# OpenBookReader_v57.net
KiCad netlist of a schematic drawn in EAGLE
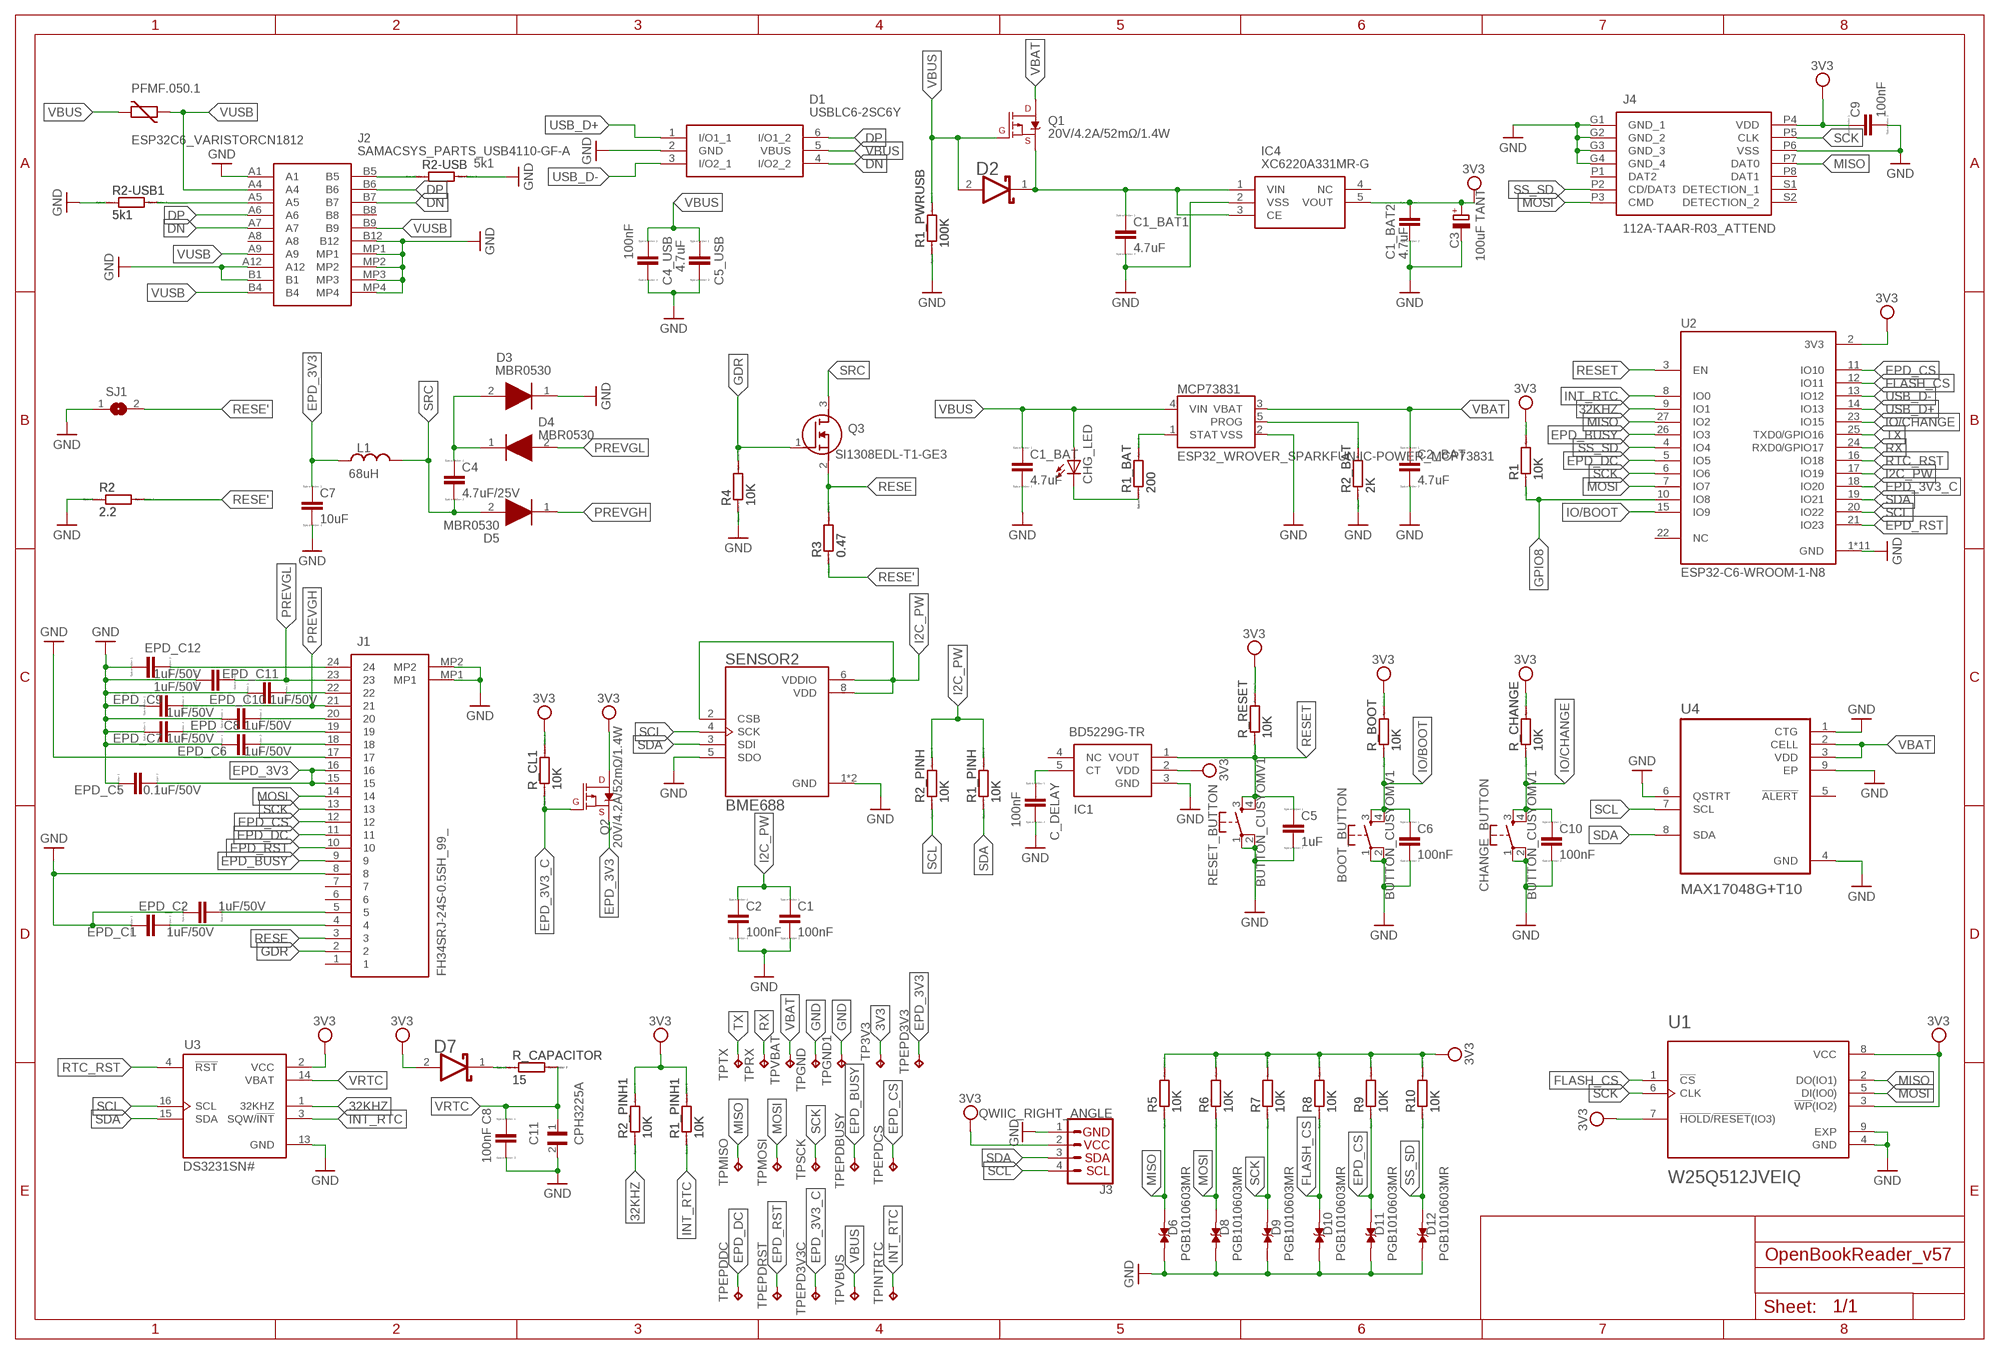
[diagram p0: schematic, sheet 1]

(export (version "E")
  (design (tool "Eeschema 10.0.6"))
  (components
    (comp (ref "BOOT_BUTTON")
      (value "BUTTON_CUSYOMV1")
      (footprint "eagle-import:MYBUTTON")
      (libsource (lib "eagle-import") (part "BUTTON_CUSYOMV1"))
    )
    (comp (ref "C1")
      (value "100nF")
      (footprint "eagle-import:EAGLE-LTSPICE_C0402")
      (libsource (lib "eagle-import") (part "EAGLE-LTSPICE_CC0402"))
    )
    (comp (ref "C1_BAT")
      (value "4.7uF")
      (footprint "eagle-import:EAGLE-LTSPICE_C0402")
      (libsource (lib "eagle-import") (part "EAGLE-LTSPICE_CC0402"))
    )
    (comp (ref "C1_BAT1")
      (value "4.7uF")
      (footprint "eagle-import:EAGLE-LTSPICE_C0402")
      (libsource (lib "eagle-import") (part "EAGLE-LTSPICE_CC0402"))
    )
    (comp (ref "C1_BAT2")
      (value "4.7uF")
      (footprint "eagle-import:EAGLE-LTSPICE_C0402")
      (libsource (lib "eagle-import") (part "EAGLE-LTSPICE_CC0402"))
    )
    (comp (ref "C2")
      (value "100nF")
      (footprint "eagle-import:EAGLE-LTSPICE_C0402")
      (libsource (lib "eagle-import") (part "EAGLE-LTSPICE_CC0402"))
    )
    (comp (ref "C2_BAT")
      (value "4.7uF")
      (footprint "eagle-import:EAGLE-LTSPICE_C0402")
      (libsource (lib "eagle-import") (part "EAGLE-LTSPICE_CC0402"))
    )
    (comp (ref "C3")
      (value "100uF TANT")
      (footprint "eagle-import:RCL_CT3528")
      (libsource (lib "eagle-import") (part "RCL_CPOL-EUCT3528"))
    )
    (comp (ref "C4")
      (value "4.7uF/25V")
      (footprint "eagle-import:EAGLE-LTSPICE_C0402")
      (libsource (lib "eagle-import") (part "EAGLE-LTSPICE_CC0402"))
    )
    (comp (ref "C4_USB")
      (value "100nF")
      (footprint "eagle-import:EAGLE-LTSPICE_C0402")
      (libsource (lib "eagle-import") (part "EAGLE-LTSPICE_CC0402"))
    )
    (comp (ref "C5")
      (value "1uF")
      (footprint "eagle-import:EAGLE-LTSPICE_C0402")
      (libsource (lib "eagle-import") (part "EAGLE-LTSPICE_CC0402"))
    )
    (comp (ref "C5_USB")
      (value "4.7uF")
      (footprint "eagle-import:EAGLE-LTSPICE_C0402")
      (libsource (lib "eagle-import") (part "EAGLE-LTSPICE_CC0402"))
    )
    (comp (ref "C6")
      (value "100nF")
      (footprint "eagle-import:EAGLE-LTSPICE_C0402")
      (libsource (lib "eagle-import") (part "EAGLE-LTSPICE_CC0402"))
    )
    (comp (ref "C7")
      (value "10uF")
      (footprint "eagle-import:EAGLE-LTSPICE_C0402")
      (libsource (lib "eagle-import") (part "EAGLE-LTSPICE_CC0402"))
    )
    (comp (ref "C8")
      (value "100nF")
      (footprint "eagle-import:EAGLE-LTSPICE_C0402")
      (libsource (lib "eagle-import") (part "EAGLE-LTSPICE_CC0402"))
    )
    (comp (ref "C9")
      (value "100nF")
      (footprint "eagle-import:EAGLE-LTSPICE_C0402")
      (libsource (lib "eagle-import") (part "EAGLE-LTSPICE_CC0402"))
    )
    (comp (ref "C10")
      (value "100nF")
      (footprint "eagle-import:EAGLE-LTSPICE_C0402")
      (libsource (lib "eagle-import") (part "EAGLE-LTSPICE_CC0402"))
    )
    (comp (ref "C11")
      (value "CPH3225A")
      (footprint "eagle-import:CAPCP3225X100N")
      (fields (field (name "MF") "Seiko Instruments"))
      (libsource (lib "eagle-import") (part "CPH3225A"))
    )
    (comp (ref "CHANGE_BUTTON")
      (value "BUTTON_CUSYOMV1")
      (footprint "eagle-import:MYBUTTON")
      (libsource (lib "eagle-import") (part "BUTTON_CUSYOMV1"))
    )
    (comp (ref "CHG_LED")
      (value "ADAFRUIT_LEDCHIP-LED0603")
      (footprint "eagle-import:ADAFRUIT_CHIP-LED0603")
      (libsource (lib "eagle-import") (part "ADAFRUIT_LEDCHIP-LED0603"))
    )
    (comp (ref "C_DELAY")
      (value "100nF")
      (footprint "eagle-import:EAGLE-LTSPICE_C0402")
      (libsource (lib "eagle-import") (part "EAGLE-LTSPICE_CC0402"))
    )
    (comp (ref "D1")
      (value "USBLC6-2SC6Y")
      (footprint "eagle-import:SOT95P280X145-6N")
      (fields (field (name "MF") "STMicroelectronics"))
      (libsource (lib "eagle-import") (part "USBLC6-2SC6Y"))
    )
    (comp (ref "D2")
      (value "ESP32_WROVER_AVX---SD0805S020S1R0_AVX_SD0805S020S1R0_0_0AVX_SD0805S020S1R0_0_0")
      (footprint "eagle-import:ESP32_WROVER_AVX---SD0805S020S1R0_AVX_SD0805S020S1R0_0")
      (fields
        (field (name "DIGIKEY_PART_NUMBER") "478-7800-1-ND")
        (field (name "MF") "AVX")
        (field (name "MOUSER_PART_NUMBER") "581-SD0805S020S1R0")
      )
      (libsource (lib "eagle-import") (part "ESP32_WROVER_AVX---SD0805S020S1R0_AVX_SD0805S020S1R0_0_0AVX_SD0805S020S1R0_0_0"))
    )
    (comp (ref "D3")
      (value "MBR0530")
      (footprint "eagle-import:SOD3716X135N")
      (fields (field (name "MF") "ON Semiconductor"))
      (libsource (lib "eagle-import") (part "MBR0530"))
    )
    (comp (ref "D4")
      (value "MBR0530")
      (footprint "eagle-import:SOD3716X135N")
      (fields (field (name "MF") "ON Semiconductor"))
      (libsource (lib "eagle-import") (part "MBR0530"))
    )
    (comp (ref "D5")
      (value "MBR0530")
      (footprint "eagle-import:SOD3716X135N")
      (fields (field (name "MF") "ON Semiconductor"))
      (libsource (lib "eagle-import") (part "MBR0530"))
    )
    (comp (ref "D6")
      (value "PGB1010603MR")
      (footprint "eagle-import:DIOC1608X36N")
      (fields (field (name "MF") "Littelfuse Inc."))
      (libsource (lib "eagle-import") (part "PGB1010603MR"))
    )
    (comp (ref "D7")
      (value "ESP32_WROVER_AVX---SD0805S020S1R0_AVX_SD0805S020S1R0_0_0AVX_SD0805S020S1R0_0_0")
      (footprint "eagle-import:ESP32_WROVER_AVX---SD0805S020S1R0_AVX_SD0805S020S1R0_0")
      (fields
        (field (name "DIGIKEY_PART_NUMBER") "478-7800-1-ND")
        (field (name "MF") "AVX")
        (field (name "MOUSER_PART_NUMBER") "581-SD0805S020S1R0")
      )
      (libsource (lib "eagle-import") (part "ESP32_WROVER_AVX---SD0805S020S1R0_AVX_SD0805S020S1R0_0_0AVX_SD0805S020S1R0_0_0"))
    )
    (comp (ref "D8")
      (value "PGB1010603MR")
      (footprint "eagle-import:DIOC1608X36N")
      (fields (field (name "MF") "Littelfuse Inc."))
      (libsource (lib "eagle-import") (part "PGB1010603MR"))
    )
    (comp (ref "D9")
      (value "PGB1010603MR")
      (footprint "eagle-import:DIOC1608X36N")
      (fields (field (name "MF") "Littelfuse Inc."))
      (libsource (lib "eagle-import") (part "PGB1010603MR"))
    )
    (comp (ref "D10")
      (value "PGB1010603MR")
      (footprint "eagle-import:DIOC1608X36N")
      (fields (field (name "MF") "Littelfuse Inc."))
      (libsource (lib "eagle-import") (part "PGB1010603MR"))
    )
    (comp (ref "D11")
      (value "PGB1010603MR")
      (footprint "eagle-import:DIOC1608X36N")
      (fields (field (name "MF") "Littelfuse Inc."))
      (libsource (lib "eagle-import") (part "PGB1010603MR"))
    )
    (comp (ref "D12")
      (value "PGB1010603MR")
      (footprint "eagle-import:DIOC1608X36N")
      (fields (field (name "MF") "Littelfuse Inc."))
      (libsource (lib "eagle-import") (part "PGB1010603MR"))
    )
    (comp (ref "EPD_C1")
      (value "1uF/50V")
      (footprint "eagle-import:EAGLE-LTSPICE_C0402")
      (libsource (lib "eagle-import") (part "EAGLE-LTSPICE_CC0402"))
    )
    (comp (ref "EPD_C2")
      (value "1uF/50V")
      (footprint "eagle-import:EAGLE-LTSPICE_C0402")
      (libsource (lib "eagle-import") (part "EAGLE-LTSPICE_CC0402"))
    )
    (comp (ref "EPD_C5")
      (value "0.1uF/50V")
      (footprint "eagle-import:EAGLE-LTSPICE_C0402")
      (libsource (lib "eagle-import") (part "EAGLE-LTSPICE_CC0402"))
    )
    (comp (ref "EPD_C6")
      (value "1uF/50V")
      (footprint "eagle-import:EAGLE-LTSPICE_C0402")
      (libsource (lib "eagle-import") (part "EAGLE-LTSPICE_CC0402"))
    )
    (comp (ref "EPD_C7")
      (value "1uF/50V")
      (footprint "eagle-import:EAGLE-LTSPICE_C0402")
      (libsource (lib "eagle-import") (part "EAGLE-LTSPICE_CC0402"))
    )
    (comp (ref "EPD_C8")
      (value "1uF/50V")
      (footprint "eagle-import:EAGLE-LTSPICE_C0402")
      (libsource (lib "eagle-import") (part "EAGLE-LTSPICE_CC0402"))
    )
    (comp (ref "EPD_C9")
      (value "1uF/50V")
      (footprint "eagle-import:EAGLE-LTSPICE_C0402")
      (libsource (lib "eagle-import") (part "EAGLE-LTSPICE_CC0402"))
    )
    (comp (ref "EPD_C10")
      (value "1uF/50V")
      (footprint "eagle-import:EAGLE-LTSPICE_C0402")
      (libsource (lib "eagle-import") (part "EAGLE-LTSPICE_CC0402"))
    )
    (comp (ref "EPD_C11")
      (value "1uF/50V")
      (footprint "eagle-import:EAGLE-LTSPICE_C0402")
      (libsource (lib "eagle-import") (part "EAGLE-LTSPICE_CC0402"))
    )
    (comp (ref "EPD_C12")
      (value "1uF/50V")
      (footprint "eagle-import:EAGLE-LTSPICE_C0402")
      (libsource (lib "eagle-import") (part "EAGLE-LTSPICE_CC0402"))
    )
    (comp (ref "IC1")
      (value "BD5229G-TR")
      (footprint "eagle-import:SOT95P280X125-5N")
      (fields (field (name "MOUSER_PART_NUMBER") "755-BD5229G-TR"))
      (libsource (lib "eagle-import") (part "BD5229G-TR"))
    )
    (comp (ref "IC4")
      (value "XC6220A331MR-G")
      (footprint "eagle-import:SOT95P280X120-5N")
      (fields (field (name "MOUSER_PART_NUMBER") "865-XC6220A331MR-G"))
      (libsource (lib "eagle-import") (part "XC6220A331MR-G"))
    )
    (comp (ref "J1")
      (value "FH34SRJ-24S-0.5SH_99_")
      (footprint "eagle-import:FH34SRJ24S05SH99")
      (fields
        (field (name "MANUFACTURER_PART_NUMBER") "FH34SRJ-24S-0.5SH(99)")
        (field (name "MOUSER_PART_NUMBER") "798-FH34SRJ24S05SH99")
      )
      (libsource (lib "eagle-import") (part "FH34SRJ-24S-0.5SH_99_"))
    )
    (comp (ref "J2")
      (value "SAMACSYS_PARTS_USB4110-GF-A")
      (footprint "eagle-import:SAMACSYS_PARTS_USB4110GFA")
      (fields
        (field (name "MANUFACTURER_PART_NUMBER") "USB4110-GF-A")
        (field (name "MOUSER_PART_NUMBER") "640-USB4110-GF-A")
      )
      (libsource (lib "eagle-import") (part "SAMACSYS_PARTS_USB4110-GF-A"))
    )
    (comp (ref "J3")
      (value "QWIIC_RIGHT_ANGLE")
      (footprint "eagle-import:JST04_1MM_RA")
      (libsource (lib "eagle-import") (part "QWIIC_CONNECTORJS-1MM"))
    )
    (comp (ref "J4")
      (value "112A-TAAR-R03_ATTEND")
      (footprint "eagle-import:112ATAARR03ATTEND")
      (fields (field (name "MANUFACTURER_PART_NUMBER") "112A-TAAR-R03 ATTEND"))
      (libsource (lib "eagle-import") (part "112A-TAAR-R03_ATTEND"))
    )
    (comp (ref "L1")
      (value "68uH")
      (footprint "eagle-import:INDC1006X60N")
      (libsource (lib "eagle-import") (part "INDUCTORCHIP-0402(1006-METRIC)_"))
    )
    (comp (ref "MCP73831")
      (value "ESP32_WROVER_SPARKFUN-IC-POWER_MCP73831")
      (footprint "eagle-import:ESP32_WROVER_SPARKFUN-IC-POWER_SOT23-5")
      (libsource (lib "eagle-import") (part "ESP32_WROVER_SPARKFUN-IC-POWER_MCP73831"))
    )
    (comp (ref "PFMF.050.1")
      (value "ESP32C6_VARISTORCN1812")
      (footprint "eagle-import:ESP32C6_VARISTOR_CT_CN1812")
      (libsource (lib "eagle-import") (part "ESP32C6_VARISTORCN1812"))
    )
    (comp (ref "Q1")
      (value "20V/4.2A/52mΩ/1.4W")
      (footprint "eagle-import:ESP32_WROVER_SPARKFUN-DISCRETESEMI_SOT23-3")
      (libsource (lib "eagle-import") (part "ESP32_WROVER_SPARKFUN-DISCRETESEMI_MOSFET_PCH-DMG2305UX-7"))
    )
    (comp (ref "Q2")
      (value "20V/4.2A/52mΩ/1.4W")
      (footprint "eagle-import:ESP32_WROVER_SPARKFUN-DISCRETESEMI_SOT23-3")
      (libsource (lib "eagle-import") (part "ESP32_WROVER_SPARKFUN-DISCRETESEMI_MOSFET_PCH-DMG2305UX-7"))
    )
    (comp (ref "Q3")
      (value "SI1308EDL-T1-GE3")
      (footprint "eagle-import:SOT65P210X110-3N")
      (fields (field (name "MF") "Vishay Siliconix"))
      (libsource (lib "eagle-import") (part "SI1308EDL-T1-GE3"))
    )
    (comp (ref "R1")
      (value "10K")
      (footprint "eagle-import:ESP32_WROVER_EAGLE-LTSPICE_R0402")
      (libsource (lib "eagle-import") (part "ESP32_WROVER_EAGLE-LTSPICE_RR0402"))
    )
    (comp (ref "R1_BAT")
      (value "200")
      (footprint "eagle-import:ESP32_WROVER_EAGLE-LTSPICE_R0402")
      (libsource (lib "eagle-import") (part "ESP32_WROVER_EAGLE-LTSPICE_RR0402"))
    )
    (comp (ref "R1_PINH")
      (value "10K")
      (footprint "eagle-import:ESP32_WROVER_EAGLE-LTSPICE_R0402")
      (libsource (lib "eagle-import") (part "ESP32_WROVER_EAGLE-LTSPICE_RR0402"))
    )
    (comp (ref "R1_PINH1")
      (value "10K")
      (footprint "eagle-import:ESP32_WROVER_EAGLE-LTSPICE_R0402")
      (libsource (lib "eagle-import") (part "ESP32_WROVER_EAGLE-LTSPICE_RR0402"))
    )
    (comp (ref "R1_PWRUSB")
      (value "100K")
      (footprint "eagle-import:ESP32_WROVER_EAGLE-LTSPICE_R0402")
      (libsource (lib "eagle-import") (part "ESP32_WROVER_EAGLE-LTSPICE_RR0402"))
    )
    (comp (ref "R2")
      (value "2.2")
      (footprint "eagle-import:ESP32_WROVER_EAGLE-LTSPICE_R0402")
      (libsource (lib "eagle-import") (part "ESP32_WROVER_EAGLE-LTSPICE_RR0402"))
    )
    (comp (ref "R2-USB")
      (value "5k1")
      (footprint "eagle-import:ESP32_WROVER_EAGLE-LTSPICE_R0402")
      (libsource (lib "eagle-import") (part "ESP32_WROVER_EAGLE-LTSPICE_RR0402"))
    )
    (comp (ref "R2-USB1")
      (value "5k1")
      (footprint "eagle-import:ESP32_WROVER_EAGLE-LTSPICE_R0402")
      (libsource (lib "eagle-import") (part "ESP32_WROVER_EAGLE-LTSPICE_RR0402"))
    )
    (comp (ref "R2_BAT")
      (value "2K")
      (footprint "eagle-import:ESP32_WROVER_EAGLE-LTSPICE_R0402")
      (libsource (lib "eagle-import") (part "ESP32_WROVER_EAGLE-LTSPICE_RR0402"))
    )
    (comp (ref "R2_PINH")
      (value "10K")
      (footprint "eagle-import:ESP32_WROVER_EAGLE-LTSPICE_R0402")
      (libsource (lib "eagle-import") (part "ESP32_WROVER_EAGLE-LTSPICE_RR0402"))
    )
    (comp (ref "R2_PINH1")
      (value "10K")
      (footprint "eagle-import:ESP32_WROVER_EAGLE-LTSPICE_R0402")
      (libsource (lib "eagle-import") (part "ESP32_WROVER_EAGLE-LTSPICE_RR0402"))
    )
    (comp (ref "R3")
      (value "0.47")
      (footprint "eagle-import:ESP32_WROVER_EAGLE-LTSPICE_R0402")
      (libsource (lib "eagle-import") (part "ESP32_WROVER_EAGLE-LTSPICE_RR0402"))
    )
    (comp (ref "R4")
      (value "10K")
      (footprint "eagle-import:ESP32_WROVER_EAGLE-LTSPICE_R0402")
      (libsource (lib "eagle-import") (part "ESP32_WROVER_EAGLE-LTSPICE_RR0402"))
    )
    (comp (ref "R5")
      (value "10K")
      (footprint "eagle-import:ESP32_WROVER_EAGLE-LTSPICE_R0402")
      (libsource (lib "eagle-import") (part "ESP32_WROVER_EAGLE-LTSPICE_RR0402"))
    )
    (comp (ref "R6")
      (value "10K")
      (footprint "eagle-import:ESP32_WROVER_EAGLE-LTSPICE_R0402")
      (libsource (lib "eagle-import") (part "ESP32_WROVER_EAGLE-LTSPICE_RR0402"))
    )
    (comp (ref "R7")
      (value "10K")
      (footprint "eagle-import:ESP32_WROVER_EAGLE-LTSPICE_R0402")
      (libsource (lib "eagle-import") (part "ESP32_WROVER_EAGLE-LTSPICE_RR0402"))
    )
    (comp (ref "R8")
      (value "10K")
      (footprint "eagle-import:ESP32_WROVER_EAGLE-LTSPICE_R0402")
      (libsource (lib "eagle-import") (part "ESP32_WROVER_EAGLE-LTSPICE_RR0402"))
    )
    (comp (ref "R9")
      (value "10K")
      (footprint "eagle-import:ESP32_WROVER_EAGLE-LTSPICE_R0402")
      (libsource (lib "eagle-import") (part "ESP32_WROVER_EAGLE-LTSPICE_RR0402"))
    )
    (comp (ref "R10")
      (value "10K")
      (footprint "eagle-import:ESP32_WROVER_EAGLE-LTSPICE_R0402")
      (libsource (lib "eagle-import") (part "ESP32_WROVER_EAGLE-LTSPICE_RR0402"))
    )
    (comp (ref "RESET_BUTTON")
      (value "BUTTON_CUSYOMV1")
      (footprint "eagle-import:MYBUTTON")
      (libsource (lib "eagle-import") (part "BUTTON_CUSYOMV1"))
    )
    (comp (ref "R_BOOT")
      (value "10K")
      (footprint "eagle-import:ESP32_WROVER_EAGLE-LTSPICE_R0402")
      (libsource (lib "eagle-import") (part "ESP32_WROVER_EAGLE-LTSPICE_RR0402"))
    )
    (comp (ref "R_CAPACITOR")
      (value "15")
      (footprint "eagle-import:ESP32_WROVER_EAGLE-LTSPICE_R0402")
      (libsource (lib "eagle-import") (part "ESP32_WROVER_EAGLE-LTSPICE_RR0402"))
    )
    (comp (ref "R_CHANGE")
      (value "10K")
      (footprint "eagle-import:ESP32_WROVER_EAGLE-LTSPICE_R0402")
      (libsource (lib "eagle-import") (part "ESP32_WROVER_EAGLE-LTSPICE_RR0402"))
    )
    (comp (ref "R_CL1")
      (value "10K")
      (footprint "eagle-import:ESP32_WROVER_EAGLE-LTSPICE_R0402")
      (libsource (lib "eagle-import") (part "ESP32_WROVER_EAGLE-LTSPICE_RR0402"))
    )
    (comp (ref "R_RESET")
      (value "10K")
      (footprint "eagle-import:ESP32_WROVER_EAGLE-LTSPICE_R0402")
      (libsource (lib "eagle-import") (part "ESP32_WROVER_EAGLE-LTSPICE_RR0402"))
    )
    (comp (ref "SENSOR2")
      (value "BME688")
      (footprint "eagle-import:ESP32_WROVER_BME680_PSON80P300X300X100-8N")
      (fields (field (name "MF") "Bosch Sensortec") (field (name "MP") "BME680"))
      (libsource (lib "eagle-import") (part "ESP32_WROVER_BME680_BME680"))
    )
    (comp (ref "SJ1") (value "SJ") (footprint "eagle-import:SJ") (libsource (lib "eagle-import") (part "SJ")))
    (comp (ref "TP3V3")
      (value "TPTP20R")
      (footprint "eagle-import:TP20R")
      (libsource (lib "eagle-import") (part "TPTP20R"))
    )
    (comp (ref "TPEPD3V3")
      (value "TPTP20R")
      (footprint "eagle-import:TP20R")
      (libsource (lib "eagle-import") (part "TPTP20R"))
    )
    (comp (ref "TPEPD3V3C")
      (value "TPTP20R")
      (footprint "eagle-import:TP20R")
      (libsource (lib "eagle-import") (part "TPTP20R"))
    )
    (comp (ref "TPEPDBUSY")
      (value "TPTP20R")
      (footprint "eagle-import:TP20R")
      (libsource (lib "eagle-import") (part "TPTP20R"))
    )
    (comp (ref "TPEPDCS")
      (value "TPTP20R")
      (footprint "eagle-import:TP20R")
      (libsource (lib "eagle-import") (part "TPTP20R"))
    )
    (comp (ref "TPEPDDC")
      (value "TPTP20R")
      (footprint "eagle-import:TP20R")
      (libsource (lib "eagle-import") (part "TPTP20R"))
    )
    (comp (ref "TPEPDRST")
      (value "TPTP20R")
      (footprint "eagle-import:TP20R")
      (libsource (lib "eagle-import") (part "TPTP20R"))
    )
    (comp (ref "TPGND")
      (value "TPTP20R")
      (footprint "eagle-import:TP20R")
      (libsource (lib "eagle-import") (part "TPTP20R"))
    )
    (comp (ref "TPGND1")
      (value "TPTP20R")
      (footprint "eagle-import:TP20R")
      (libsource (lib "eagle-import") (part "TPTP20R"))
    )
    (comp (ref "TPINTRTC")
      (value "TPTP20R")
      (footprint "eagle-import:TP20R")
      (libsource (lib "eagle-import") (part "TPTP20R"))
    )
    (comp (ref "TPMISO")
      (value "TPTP20R")
      (footprint "eagle-import:TP20R")
      (libsource (lib "eagle-import") (part "TPTP20R"))
    )
    (comp (ref "TPMOSI")
      (value "TPTP20R")
      (footprint "eagle-import:TP20R")
      (libsource (lib "eagle-import") (part "TPTP20R"))
    )
    (comp (ref "TPRX")
      (value "TPTP20R")
      (footprint "eagle-import:TP20R")
      (libsource (lib "eagle-import") (part "TPTP20R"))
    )
    (comp (ref "TPSCK")
      (value "TPTP20R")
      (footprint "eagle-import:TP20R")
      (libsource (lib "eagle-import") (part "TPTP20R"))
    )
    (comp (ref "TPTX")
      (value "TPTP20R")
      (footprint "eagle-import:TP20R")
      (libsource (lib "eagle-import") (part "TPTP20R"))
    )
    (comp (ref "TPVBAT")
      (value "TPTP20R")
      (footprint "eagle-import:TP20R")
      (libsource (lib "eagle-import") (part "TPTP20R"))
    )
    (comp (ref "TPVBUS")
      (value "TPTP20R")
      (footprint "eagle-import:TP20R")
      (libsource (lib "eagle-import") (part "TPTP20R"))
    )
    (comp (ref "U1")
      (value "W25Q512JVEIQ")
      (footprint "eagle-import:SON127P600X800X80-9N")
      (fields (field (name "MF") "Winbond Electronics"))
      (libsource (lib "eagle-import") (part "W25Q512JVEIQ"))
    )
    (comp (ref "U2")
      (value "ESP32-C6-WROOM-1-N8")
      (footprint "eagle-import:XCVR_ESP32-C6-WROOM-1-N8")
      (fields (field (name "MF") "Espressif Systems"))
      (libsource (lib "eagle-import") (part "ESP32-C6-WROOM-1-N8"))
    )
    (comp (ref "U3")
      (value "DS3231SN#")
      (footprint "eagle-import:SOIC127P1032X265-16N")
      (fields (field (name "MF") "Analog Devices"))
      (libsource (lib "eagle-import") (part "DS3231SN#"))
    )
    (comp (ref "U4")
      (value "MAX17048G+T10")
      (footprint "eagle-import:SON50P200X200X80-9N")
      (fields (field (name "MF") "Analog Devices"))
      (libsource (lib "eagle-import") (part "MAX17048G+T10"))
    )
  )
  (nets
    (net (code "1") (name "3V3") (class "Default")
      (node (ref "C1_BAT2") (pin "1") (pinfunction "1_1") (pintype "passive"))
      (node (ref "C3") (pin "+") (pinfunction "+_+") (pintype "passive"))
      (node (ref "C9") (pin "1") (pinfunction "1_1") (pintype "passive"))
      (node (ref "D7") (pin "2") (pinfunction "ANODE_2") (pintype "bidirectional"))
      (node (ref "IC1") (pin "2") (pinfunction "VDD_2") (pintype "bidirectional"))
      (node (ref "IC4") (pin "5") (pinfunction "VOUT_5") (pintype "bidirectional"))
      (node (ref "J3") (pin "2") (pinfunction "2_2") (pintype "power_in"))
      (node (ref "J4") (pin "P4") (pinfunction "VDD_P4") (pintype "bidirectional"))
      (node (ref "Q2") (pin "3") (pinfunction "D_3") (pintype "bidirectional"))
      (node (ref "R1") (pin "2") (pinfunction "2_2") (pintype "passive"))
      (node (ref "R10") (pin "2") (pinfunction "2_2") (pintype "passive"))
      (node (ref "R1_PINH1") (pin "2") (pinfunction "2_2") (pintype "passive"))
      (node (ref "R2_PINH1") (pin "2") (pinfunction "2_2") (pintype "passive"))
      (node (ref "R5") (pin "2") (pinfunction "2_2") (pintype "passive"))
      (node (ref "R6") (pin "2") (pinfunction "2_2") (pintype "passive"))
      (node (ref "R7") (pin "2") (pinfunction "2_2") (pintype "passive"))
      (node (ref "R8") (pin "2") (pinfunction "2_2") (pintype "passive"))
      (node (ref "R9") (pin "2") (pinfunction "2_2") (pintype "passive"))
      (node (ref "R_BOOT") (pin "2") (pinfunction "2_2") (pintype "passive"))
      (node (ref "R_CHANGE") (pin "2") (pinfunction "2_2") (pintype "passive"))
      (node (ref "R_CL1") (pin "2") (pinfunction "2_2") (pintype "passive"))
      (node (ref "R_RESET") (pin "2") (pinfunction "2_2") (pintype "passive"))
      (node (ref "TP3V3") (pin "TP") (pinfunction "TP_TP") (pintype "input"))
      (node (ref "U1") (pin "3") (pinfunction "~{WP}(IO2)_3") (pintype "bidirectional"))
      (node (ref "U1") (pin "7") (pinfunction "~{HOLD}/~{RESET}(IO3)_7") (pintype "bidirectional"))
      (node (ref "U1") (pin "8") (pinfunction "VCC_8") (pintype "power_in"))
      (node (ref "U2") (pin "2") (pinfunction "3V3_2") (pintype "power_in"))
      (node (ref "U3") (pin "2") (pinfunction "VCC_2") (pintype "power_in"))
    )
    (net (code "2") (name "32KHZ") (class "Default")
      (node (ref "R2_PINH1") (pin "1") (pinfunction "1_1") (pintype "passive"))
      (node (ref "U2") (pin "9") (pinfunction "IO1_9") (pintype "bidirectional"))
      (node (ref "U3") (pin "1") (pinfunction "32KHZ_1") (pintype "output"))
    )
    (net (code "3") (name "DN") (class "Default")
      (node (ref "D1") (pin "4") (pinfunction "I/O2_2_4") (pintype "bidirectional"))
      (node (ref "J2") (pin "A7") (pinfunction "A7_A7") (pintype "bidirectional"))
      (node (ref "J2") (pin "B7") (pinfunction "B7_B7") (pintype "bidirectional"))
    )
    (net (code "4") (name "DP") (class "Default")
      (node (ref "D1") (pin "6") (pinfunction "I/O1_2_6") (pintype "bidirectional"))
      (node (ref "J2") (pin "A6") (pinfunction "A6_A6") (pintype "bidirectional"))
      (node (ref "J2") (pin "B6") (pinfunction "B6_B6") (pintype "bidirectional"))
    )
    (net (code "5") (name "EPD_3V3") (class "Default")
      (node (ref "C7") (pin "1") (pinfunction "1_1") (pintype "passive"))
      (node (ref "EPD_C5") (pin "2") (pinfunction "2_2") (pintype "passive"))
      (node (ref "J1") (pin "15") (pinfunction "15_15") (pintype "bidirectional"))
      (node (ref "J1") (pin "16") (pinfunction "16_16") (pintype "bidirectional"))
      (node (ref "L1") (pin "1") (pinfunction "1_1") (pintype "passive"))
      (node (ref "Q2") (pin "2") (pinfunction "S_2") (pintype "bidirectional"))
      (node (ref "TPEPD3V3") (pin "TP") (pinfunction "TP_TP") (pintype "input"))
    )
    (net (code "6") (name "EPD_3V3_C") (class "Default")
      (node (ref "Q2") (pin "1") (pinfunction "G_1") (pintype "bidirectional"))
      (node (ref "R_CL1") (pin "1") (pinfunction "1_1") (pintype "passive"))
      (node (ref "TPEPD3V3C") (pin "TP") (pinfunction "TP_TP") (pintype "input"))
      (node (ref "U2") (pin "18") (pinfunction "IO20_18") (pintype "bidirectional"))
    )
    (net (code "7") (name "EPD_BUSY") (class "Default")
      (node (ref "J1") (pin "9") (pinfunction "9_9") (pintype "bidirectional"))
      (node (ref "TPEPDBUSY") (pin "TP") (pinfunction "TP_TP") (pintype "input"))
      (node (ref "U2") (pin "26") (pinfunction "IO3_26") (pintype "bidirectional"))
    )
    (net (code "8") (name "EPD_CS") (class "Default")
      (node (ref "D11") (pin "2") (pinfunction "2_2") (pintype "passive"))
      (node (ref "J1") (pin "12") (pinfunction "12_12") (pintype "bidirectional"))
      (node (ref "R9") (pin "1") (pinfunction "1_1") (pintype "passive"))
      (node (ref "TPEPDCS") (pin "TP") (pinfunction "TP_TP") (pintype "input"))
      (node (ref "U2") (pin "11") (pinfunction "IO10_11") (pintype "bidirectional"))
    )
    (net (code "9") (name "EPD_DC") (class "Default")
      (node (ref "J1") (pin "11") (pinfunction "11_11") (pintype "bidirectional"))
      (node (ref "TPEPDDC") (pin "TP") (pinfunction "TP_TP") (pintype "input"))
      (node (ref "U2") (pin "5") (pinfunction "IO5_5") (pintype "bidirectional"))
    )
    (net (code "10") (name "EPD_RST") (class "Default")
      (node (ref "J1") (pin "10") (pinfunction "10_10") (pintype "bidirectional"))
      (node (ref "TPEPDRST") (pin "TP") (pinfunction "TP_TP") (pintype "input"))
      (node (ref "U2") (pin "21") (pinfunction "IO23_21") (pintype "bidirectional"))
    )
    (net (code "11") (name "FLASH_CS") (class "Default")
      (node (ref "D10") (pin "2") (pinfunction "2_2") (pintype "passive"))
      (node (ref "R8") (pin "1") (pinfunction "1_1") (pintype "passive"))
      (node (ref "U1") (pin "1") (pinfunction "~{CS}_1") (pintype "input"))
      (node (ref "U2") (pin "12") (pinfunction "IO11_12") (pintype "bidirectional"))
    )
    (net (code "12") (name "GDR") (class "Default")
      (node (ref "J1") (pin "2") (pinfunction "2_2") (pintype "bidirectional"))
      (node (ref "Q3") (pin "1") (pinfunction "G_1") (pintype "bidirectional"))
      (node (ref "R4") (pin "2") (pinfunction "2_2") (pintype "passive"))
    )
    (net (code "13") (name "GND") (class "Default")
      (node (ref "BOOT_BUTTON") (pin "1") (pinfunction "1_1") (pintype "passive"))
      (node (ref "BOOT_BUTTON") (pin "2") (pinfunction "2_2") (pintype "passive"))
      (node (ref "C1") (pin "2") (pinfunction "2_2") (pintype "passive"))
      (node (ref "C10") (pin "2") (pinfunction "2_2") (pintype "passive"))
      (node (ref "C11") (pin "2") (pinfunction "2_2") (pintype "passive"))
      (node (ref "C1_BAT") (pin "2") (pinfunction "2_2") (pintype "passive"))
      (node (ref "C1_BAT1") (pin "2") (pinfunction "2_2") (pintype "passive"))
      (node (ref "C1_BAT2") (pin "2") (pinfunction "2_2") (pintype "passive"))
      (node (ref "C2") (pin "2") (pinfunction "2_2") (pintype "passive"))
      (node (ref "C2_BAT") (pin "2") (pinfunction "2_2") (pintype "passive"))
      (node (ref "C3") (pin "-") (pinfunction "-_-") (pintype "passive"))
      (node (ref "C4_USB") (pin "2") (pinfunction "2_2") (pintype "passive"))
      (node (ref "C5") (pin "2") (pinfunction "2_2") (pintype "passive"))
      (node (ref "C5_USB") (pin "2") (pinfunction "2_2") (pintype "passive"))
      (node (ref "C6") (pin "2") (pinfunction "2_2") (pintype "passive"))
      (node (ref "C7") (pin "2") (pinfunction "2_2") (pintype "passive"))
      (node (ref "C8") (pin "2") (pinfunction "2_2") (pintype "passive"))
      (node (ref "C9") (pin "2") (pinfunction "2_2") (pintype "passive"))
      (node (ref "CHANGE_BUTTON") (pin "1") (pinfunction "1_1") (pintype "passive"))
      (node (ref "CHANGE_BUTTON") (pin "2") (pinfunction "2_2") (pintype "passive"))
      (node (ref "C_DELAY") (pin "2") (pinfunction "2_2") (pintype "passive"))
      (node (ref "D1") (pin "2") (pinfunction "GND_2") (pintype "bidirectional"))
      (node (ref "D10") (pin "1") (pinfunction "1_1") (pintype "passive"))
      (node (ref "D11") (pin "1") (pinfunction "1_1") (pintype "passive"))
      (node (ref "D12") (pin "1") (pinfunction "1_1") (pintype "passive"))
      (node (ref "D3") (pin "1") (pinfunction "K_1") (pintype "bidirectional"))
      (node (ref "D6") (pin "1") (pinfunction "1_1") (pintype "passive"))
      (node (ref "D8") (pin "1") (pinfunction "1_1") (pintype "passive"))
      (node (ref "D9") (pin "1") (pinfunction "1_1") (pintype "passive"))
      (node (ref "EPD_C1") (pin "1") (pinfunction "1_1") (pintype "passive"))
      (node (ref "EPD_C10") (pin "1") (pinfunction "1_1") (pintype "passive"))
      (node (ref "EPD_C11") (pin "1") (pinfunction "1_1") (pintype "passive"))
      (node (ref "EPD_C12") (pin "1") (pinfunction "1_1") (pintype "passive"))
      (node (ref "EPD_C2") (pin "1") (pinfunction "1_1") (pintype "passive"))
      (node (ref "EPD_C5") (pin "1") (pinfunction "1_1") (pintype "passive"))
      (node (ref "EPD_C6") (pin "1") (pinfunction "1_1") (pintype "passive"))
      (node (ref "EPD_C7") (pin "1") (pinfunction "1_1") (pintype "passive"))
      (node (ref "EPD_C8") (pin "1") (pinfunction "1_1") (pintype "passive"))
      (node (ref "EPD_C9") (pin "1") (pinfunction "1_1") (pintype "passive"))
      (node (ref "IC1") (pin "3") (pinfunction "GND_3") (pintype "bidirectional"))
      (node (ref "IC4") (pin "2") (pinfunction "VSS_2") (pintype "bidirectional"))
      (node (ref "J1") (pin "17") (pinfunction "17_17") (pintype "bidirectional"))
      (node (ref "J1") (pin "8") (pinfunction "8_8") (pintype "bidirectional"))
      (node (ref "J1") (pin "MP1") (pinfunction "MP1_MP1") (pintype "bidirectional"))
      (node (ref "J1") (pin "MP2") (pinfunction "MP2_MP2") (pintype "bidirectional"))
      (node (ref "J2") (pin "A1") (pinfunction "A1_A1") (pintype "bidirectional"))
      (node (ref "J2") (pin "A12") (pinfunction "A12_A12") (pintype "bidirectional"))
      (node (ref "J2") (pin "B1") (pinfunction "B1_B1") (pintype "bidirectional"))
      (node (ref "J2") (pin "B12") (pinfunction "B12_B12") (pintype "bidirectional"))
      (node (ref "J2") (pin "MP1") (pinfunction "MP1_MP1") (pintype "bidirectional"))
      (node (ref "J2") (pin "MP2") (pinfunction "MP2_MP2") (pintype "bidirectional"))
      (node (ref "J2") (pin "MP3") (pinfunction "MP3_MP3") (pintype "bidirectional"))
      (node (ref "J2") (pin "MP4") (pinfunction "MP4_MP4") (pintype "bidirectional"))
      (node (ref "J3") (pin "1") (pinfunction "1_1") (pintype "power_in"))
      (node (ref "J4") (pin "G1") (pinfunction "GND_1_G1") (pintype "bidirectional"))
      (node (ref "J4") (pin "G2") (pinfunction "GND_2_G2") (pintype "bidirectional"))
      (node (ref "J4") (pin "G3") (pinfunction "GND_3_G3") (pintype "bidirectional"))
      (node (ref "J4") (pin "G4") (pinfunction "GND_4_G4") (pintype "bidirectional"))
      (node (ref "J4") (pin "P6") (pinfunction "VSS_P6") (pintype "bidirectional"))
      (node (ref "MCP73831") (pin "2") (pinfunction "VSS_2") (pintype "power_in"))
      (node (ref "R1_PWRUSB") (pin "1") (pinfunction "1_1") (pintype "passive"))
      (node (ref "R2") (pin "1") (pinfunction "1_1") (pintype "passive"))
      (node (ref "R2-USB") (pin "2") (pinfunction "2_2") (pintype "passive"))
      (node (ref "R2-USB1") (pin "1") (pinfunction "1_1") (pintype "passive"))
      (node (ref "R2_BAT") (pin "1") (pinfunction "1_1") (pintype "passive"))
      (node (ref "R4") (pin "1") (pinfunction "1_1") (pintype "passive"))
      (node (ref "RESET_BUTTON") (pin "1") (pinfunction "1_1") (pintype "passive"))
      (node (ref "RESET_BUTTON") (pin "2") (pinfunction "2_2") (pintype "passive"))
      (node (ref "SENSOR2") (pin "1") (pinfunction "GND_1") (pintype "power_in"))
      (node (ref "SENSOR2") (pin "5") (pinfunction "SDO_5") (pintype "bidirectional"))
      (node (ref "SENSOR2") (pin "7") (pinfunction "GND_7") (pintype "power_in"))
      (node (ref "SJ1") (pin "1") (pinfunction "1_1") (pintype "passive"))
      (node (ref "TPGND") (pin "TP") (pinfunction "TP_TP") (pintype "input"))
      (node (ref "TPGND1") (pin "TP") (pinfunction "TP_TP") (pintype "input"))
      (node (ref "U1") (pin "4") (pinfunction "GND_4") (pintype "power_in"))
      (node (ref "U1") (pin "9") (pinfunction "EXP_9") (pintype "passive"))
      (node (ref "U2") (pin "1") (pinfunction "GND_1") (pintype "power_in"))
      (node (ref "U2") (pin "28") (pinfunction "GND_28") (pintype "power_in"))
      (node (ref "U2") (pin "29_1") (pinfunction "GND_29_1") (pintype "power_in"))
      (node (ref "U2") (pin "29_2") (pinfunction "GND_29_2") (pintype "power_in"))
      (node (ref "U2") (pin "29_3") (pinfunction "GND_29_3") (pintype "power_in"))
      (node (ref "U2") (pin "29_4") (pinfunction "GND_29_4") (pintype "power_in"))
      (node (ref "U2") (pin "29_5") (pinfunction "GND_29_5") (pintype "power_in"))
      (node (ref "U2") (pin "29_6") (pinfunction "GND_29_6") (pintype "power_in"))
      (node (ref "U2") (pin "29_7") (pinfunction "GND_29_7") (pintype "power_in"))
      (node (ref "U2") (pin "29_8") (pinfunction "GND_29_8") (pintype "power_in"))
      (node (ref "U2") (pin "29_9") (pinfunction "GND_29_9") (pintype "power_in"))
      (node (ref "U3") (pin "13") (pinfunction "GND_13") (pintype "power_in"))
      (node (ref "U4") (pin "1") (pinfunction "CTG_1") (pintype "power_in"))
      (node (ref "U4") (pin "4") (pinfunction "GND_4") (pintype "power_in"))
      (node (ref "U4") (pin "6") (pinfunction "QSTRT_6") (pintype "input"))
      (node (ref "U4") (pin "9") (pinfunction "EP_9") (pintype "power_in"))
    )
    (net (code "14") (name "GPIO8") (class "Default")
      (node (ref "R1") (pin "1") (pinfunction "1_1") (pintype "passive"))
      (node (ref "U2") (pin "10") (pinfunction "IO8_10") (pintype "bidirectional"))
    )
    (net (code "15") (name "I2C_PW") (class "Default")
      (node (ref "C1") (pin "1") (pinfunction "1_1") (pintype "passive"))
      (node (ref "C2") (pin "1") (pinfunction "1_1") (pintype "passive"))
      (node (ref "R1_PINH") (pin "2") (pinfunction "2_2") (pintype "passive"))
      (node (ref "R2_PINH") (pin "2") (pinfunction "2_2") (pintype "passive"))
      (node (ref "SENSOR2") (pin "2") (pinfunction "CSB_2") (pintype "input"))
      (node (ref "SENSOR2") (pin "6") (pinfunction "VDDIO_6") (pintype "power_in"))
      (node (ref "SENSOR2") (pin "8") (pinfunction "VDD_8") (pintype "power_in"))
      (node (ref "U2") (pin "17") (pinfunction "IO19_17") (pintype "bidirectional"))
    )
    (net (code "16") (name "INT_RTC") (class "Default")
      (node (ref "R1_PINH1") (pin "1") (pinfunction "1_1") (pintype "passive"))
      (node (ref "TPINTRTC") (pin "TP") (pinfunction "TP_TP") (pintype "input"))
      (node (ref "U2") (pin "8") (pinfunction "IO0_8") (pintype "bidirectional"))
      (node (ref "U3") (pin "3") (pinfunction "SQW/~{INT}_3") (pintype "output"))
    )
    (net (code "17") (name "IO{slash}BOOT") (class "Default")
      (node (ref "BOOT_BUTTON") (pin "3") (pinfunction "3_3") (pintype "passive"))
      (node (ref "BOOT_BUTTON") (pin "4") (pinfunction "4_4") (pintype "passive"))
      (node (ref "C6") (pin "1") (pinfunction "1_1") (pintype "passive"))
      (node (ref "R_BOOT") (pin "1") (pinfunction "1_1") (pintype "passive"))
      (node (ref "U2") (pin "15") (pinfunction "IO9_15") (pintype "bidirectional"))
    )
    (net (code "18") (name "IO{slash}CHANGE") (class "Default")
      (node (ref "C10") (pin "1") (pinfunction "1_1") (pintype "passive"))
      (node (ref "CHANGE_BUTTON") (pin "3") (pinfunction "3_3") (pintype "passive"))
      (node (ref "CHANGE_BUTTON") (pin "4") (pinfunction "4_4") (pintype "passive"))
      (node (ref "R_CHANGE") (pin "1") (pinfunction "1_1") (pintype "passive"))
      (node (ref "U2") (pin "23") (pinfunction "IO15_23") (pintype "bidirectional"))
    )
    (net (code "19") (name "MISO") (class "Default")
      (node (ref "D6") (pin "2") (pinfunction "2_2") (pintype "passive"))
      (node (ref "J4") (pin "P7") (pinfunction "DAT0_P7") (pintype "bidirectional"))
      (node (ref "R5") (pin "1") (pinfunction "1_1") (pintype "passive"))
      (node (ref "TPMISO") (pin "TP") (pinfunction "TP_TP") (pintype "input"))
      (node (ref "U1") (pin "2") (pinfunction "DO(IO1)_2") (pintype "bidirectional"))
      (node (ref "U2") (pin "27") (pinfunction "IO2_27") (pintype "bidirectional"))
    )
    (net (code "20") (name "MOSI") (class "Default")
      (node (ref "D8") (pin "2") (pinfunction "2_2") (pintype "passive"))
      (node (ref "J1") (pin "14") (pinfunction "14_14") (pintype "bidirectional"))
      (node (ref "J4") (pin "P3") (pinfunction "CMD_P3") (pintype "bidirectional"))
      (node (ref "R6") (pin "1") (pinfunction "1_1") (pintype "passive"))
      (node (ref "TPMOSI") (pin "TP") (pinfunction "TP_TP") (pintype "input"))
      (node (ref "U1") (pin "5") (pinfunction "DI(IO0)_5") (pintype "bidirectional"))
      (node (ref "U2") (pin "7") (pinfunction "IO7_7") (pintype "bidirectional"))
    )
    (net (code "21") (name "Net-(CHG_LED-PadC)") (class "Default")
      (node (ref "CHG_LED") (pin "C") (pinfunction "C_C") (pintype "passive"))
      (node (ref "R1_BAT") (pin "1") (pinfunction "1_1") (pintype "passive"))
    )
    (net (code "22") (name "Net-(D2-CATHODE)") (class "Default")
      (node (ref "C1_BAT1") (pin "1") (pinfunction "1_1") (pintype "passive"))
      (node (ref "D2") (pin "1") (pinfunction "CATHODE_1") (pintype "bidirectional"))
      (node (ref "IC4") (pin "1") (pinfunction "VIN_1") (pintype "bidirectional"))
      (node (ref "IC4") (pin "3") (pinfunction "CE_3") (pintype "bidirectional"))
      (node (ref "Q1") (pin "2") (pinfunction "S_2") (pintype "bidirectional"))
    )
    (net (code "23") (name "Net-(D3-A)") (class "Default")
      (node (ref "C4") (pin "1") (pinfunction "1_1") (pintype "passive"))
      (node (ref "D3") (pin "2") (pinfunction "A_2") (pintype "bidirectional"))
      (node (ref "D4") (pin "1") (pinfunction "K_1") (pintype "bidirectional"))
    )
    (net (code "24") (name "Net-(D7-CATHODE)") (class "Default")
      (node (ref "D7") (pin "1") (pinfunction "CATHODE_1") (pintype "bidirectional"))
      (node (ref "R_CAPACITOR") (pin "1") (pinfunction "1_1") (pintype "passive"))
    )
    (net (code "25") (name "Net-(EPD_C1-Pad2)") (class "Default")
      (node (ref "EPD_C1") (pin "2") (pinfunction "2_2") (pintype "passive"))
      (node (ref "J1") (pin "4") (pinfunction "4_4") (pintype "bidirectional"))
    )
    (net (code "26") (name "Net-(EPD_C2-Pad2)") (class "Default")
      (node (ref "EPD_C2") (pin "2") (pinfunction "2_2") (pintype "passive"))
      (node (ref "J1") (pin "5") (pinfunction "5_5") (pintype "bidirectional"))
    )
    (net (code "27") (name "Net-(EPD_C6-Pad2)") (class "Default")
      (node (ref "EPD_C6") (pin "2") (pinfunction "2_2") (pintype "passive"))
      (node (ref "J1") (pin "18") (pinfunction "18_18") (pintype "bidirectional"))
    )
    (net (code "28") (name "Net-(EPD_C7-Pad2)") (class "Default")
      (node (ref "EPD_C7") (pin "2") (pinfunction "2_2") (pintype "passive"))
      (node (ref "J1") (pin "19") (pinfunction "19_19") (pintype "bidirectional"))
    )
    (net (code "29") (name "Net-(EPD_C8-Pad2)") (class "Default")
      (node (ref "EPD_C8") (pin "2") (pinfunction "2_2") (pintype "passive"))
      (node (ref "J1") (pin "20") (pinfunction "20_20") (pintype "bidirectional"))
    )
    (net (code "30") (name "Net-(EPD_C10-Pad2)") (class "Default")
      (node (ref "EPD_C10") (pin "2") (pinfunction "2_2") (pintype "passive"))
      (node (ref "J1") (pin "22") (pinfunction "22_22") (pintype "bidirectional"))
    )
    (net (code "31") (name "Net-(EPD_C12-Pad2)") (class "Default")
      (node (ref "EPD_C12") (pin "2") (pinfunction "2_2") (pintype "passive"))
      (node (ref "J1") (pin "24") (pinfunction "24_24") (pintype "bidirectional"))
    )
    (net (code "32") (name "Net-(IC1-CT)") (class "Default")
      (node (ref "C_DELAY") (pin "1") (pinfunction "1_1") (pintype "passive"))
      (node (ref "IC1") (pin "5") (pinfunction "CT_5") (pintype "bidirectional"))
    )
    (net (code "33") (name "Net-(J2-PadA5)") (class "Default")
      (node (ref "J2") (pin "A5") (pinfunction "A5_A5") (pintype "bidirectional"))
      (node (ref "R2-USB1") (pin "2") (pinfunction "2_2") (pintype "passive"))
    )
    (net (code "34") (name "Net-(J2-PadB5)") (class "Default")
      (node (ref "J2") (pin "B5") (pinfunction "B5_B5") (pintype "bidirectional"))
      (node (ref "R2-USB") (pin "1") (pinfunction "1_1") (pintype "passive"))
    )
    (net (code "35") (name "Net-(MCP73831-PROG)") (class "Default")
      (node (ref "MCP73831") (pin "5") (pinfunction "PROG_5") (pintype "input"))
      (node (ref "R2_BAT") (pin "2") (pinfunction "2_2") (pintype "passive"))
    )
    (net (code "36") (name "Net-(MCP73831-STAT)") (class "Default")
      (node (ref "MCP73831") (pin "1") (pinfunction "STAT_1") (pintype "output"))
      (node (ref "R1_BAT") (pin "2") (pinfunction "2_2") (pintype "passive"))
    )
    (net (code "37") (name "PREVGH") (class "Default")
      (node (ref "D5") (pin "1") (pinfunction "K_1") (pintype "bidirectional"))
      (node (ref "EPD_C9") (pin "2") (pinfunction "2_2") (pintype "passive"))
      (node (ref "J1") (pin "21") (pinfunction "21_21") (pintype "bidirectional"))
    )
    (net (code "38") (name "PREVGL") (class "Default")
      (node (ref "D4") (pin "2") (pinfunction "A_2") (pintype "bidirectional"))
      (node (ref "EPD_C11") (pin "2") (pinfunction "2_2") (pintype "passive"))
      (node (ref "J1") (pin "23") (pinfunction "23_23") (pintype "bidirectional"))
    )
    (net (code "39") (name "RESE") (class "Default")
      (node (ref "J1") (pin "3") (pinfunction "3_3") (pintype "bidirectional"))
      (node (ref "Q3") (pin "2") (pinfunction "S_2") (pintype "bidirectional"))
      (node (ref "R3") (pin "2") (pinfunction "2_2") (pintype "passive"))
    )
    (net (code "40") (name "RESE'") (class "Default")
      (node (ref "R2") (pin "2") (pinfunction "2_2") (pintype "passive"))
      (node (ref "R3") (pin "1") (pinfunction "1_1") (pintype "passive"))
      (node (ref "SJ1") (pin "2") (pinfunction "2_2") (pintype "passive"))
    )
    (net (code "41") (name "RESET") (class "Default")
      (node (ref "C5") (pin "1") (pinfunction "1_1") (pintype "passive"))
      (node (ref "IC1") (pin "1") (pinfunction "VOUT_1") (pintype "bidirectional"))
      (node (ref "RESET_BUTTON") (pin "3") (pinfunction "3_3") (pintype "passive"))
      (node (ref "RESET_BUTTON") (pin "4") (pinfunction "4_4") (pintype "passive"))
      (node (ref "R_RESET") (pin "1") (pinfunction "1_1") (pintype "passive"))
      (node (ref "U2") (pin "3") (pinfunction "EN_3") (pintype "input"))
    )
    (net (code "42") (name "RTC_RST") (class "Default")
      (node (ref "U2") (pin "16") (pinfunction "IO18_16") (pintype "bidirectional"))
      (node (ref "U3") (pin "4") (pinfunction "~{RST}_4") (pintype "input"))
    )
    (net (code "43") (name "RX") (class "Default")
      (node (ref "TPRX") (pin "TP") (pinfunction "TP_TP") (pintype "input"))
      (node (ref "U2") (pin "24") (pinfunction "RXD0/GPIO17_24") (pintype "bidirectional"))
    )
    (net (code "44") (name "SCK") (class "Default")
      (node (ref "D9") (pin "2") (pinfunction "2_2") (pintype "passive"))
      (node (ref "J1") (pin "13") (pinfunction "13_13") (pintype "bidirectional"))
      (node (ref "J4") (pin "P5") (pinfunction "CLK_P5") (pintype "bidirectional"))
      (node (ref "R7") (pin "1") (pinfunction "1_1") (pintype "passive"))
      (node (ref "TPSCK") (pin "TP") (pinfunction "TP_TP") (pintype "input"))
      (node (ref "U1") (pin "6") (pinfunction "CLK_6") (pintype "input"))
      (node (ref "U2") (pin "6") (pinfunction "IO6_6") (pintype "bidirectional"))
    )
    (net (code "45") (name "SCL") (class "Default")
      (node (ref "J3") (pin "4") (pinfunction "4_4") (pintype "passive"))
      (node (ref "R2_PINH") (pin "1") (pinfunction "1_1") (pintype "passive"))
      (node (ref "SENSOR2") (pin "4") (pinfunction "SCK_4") (pintype "input"))
      (node (ref "U2") (pin "20") (pinfunction "IO22_20") (pintype "bidirectional"))
      (node (ref "U3") (pin "16") (pinfunction "SCL_16") (pintype "input"))
      (node (ref "U4") (pin "7") (pinfunction "SCL_7") (pintype "input"))
    )
    (net (code "46") (name "SDA") (class "Default")
      (node (ref "J3") (pin "3") (pinfunction "3_3") (pintype "passive"))
      (node (ref "R1_PINH") (pin "1") (pinfunction "1_1") (pintype "passive"))
      (node (ref "SENSOR2") (pin "3") (pinfunction "SDI_3") (pintype "bidirectional"))
      (node (ref "U2") (pin "19") (pinfunction "IO21_19") (pintype "bidirectional"))
      (node (ref "U3") (pin "15") (pinfunction "SDA_15") (pintype "bidirectional"))
      (node (ref "U4") (pin "8") (pinfunction "SDA_8") (pintype "bidirectional"))
    )
    (net (code "47") (name "SRC") (class "Default")
      (node (ref "C4") (pin "2") (pinfunction "2_2") (pintype "passive"))
      (node (ref "D5") (pin "2") (pinfunction "A_2") (pintype "bidirectional"))
      (node (ref "L1") (pin "2") (pinfunction "2_2") (pintype "passive"))
      (node (ref "Q3") (pin "3") (pinfunction "D_3") (pintype "bidirectional"))
    )
    (net (code "48") (name "SS_SD") (class "Default")
      (node (ref "D12") (pin "2") (pinfunction "2_2") (pintype "passive"))
      (node (ref "J4") (pin "P2") (pinfunction "CD/DAT3_P2") (pintype "bidirectional"))
      (node (ref "R10") (pin "1") (pinfunction "1_1") (pintype "passive"))
      (node (ref "U2") (pin "4") (pinfunction "IO4_4") (pintype "bidirectional"))
    )
    (net (code "49") (name "TX") (class "Default")
      (node (ref "TPTX") (pin "TP") (pinfunction "TP_TP") (pintype "input"))
      (node (ref "U2") (pin "25") (pinfunction "TXD0/GPIO16_25") (pintype "bidirectional"))
    )
    (net (code "50") (name "USB_D+") (class "Default")
      (node (ref "D1") (pin "1") (pinfunction "I/O1_1_1") (pintype "bidirectional"))
      (node (ref "U2") (pin "14") (pinfunction "IO13_14") (pintype "bidirectional"))
    )
    (net (code "51") (name "USB_D-") (class "Default")
      (node (ref "D1") (pin "3") (pinfunction "I/O2_1_3") (pintype "bidirectional"))
      (node (ref "U2") (pin "13") (pinfunction "IO12_13") (pintype "bidirectional"))
    )
    (net (code "52") (name "VBAT") (class "Default")
      (node (ref "C2_BAT") (pin "1") (pinfunction "1_1") (pintype "passive"))
      (node (ref "MCP73831") (pin "3") (pinfunction "VBAT_3") (pintype "power_in"))
      (node (ref "Q1") (pin "3") (pinfunction "D_3") (pintype "bidirectional"))
      (node (ref "TPVBAT") (pin "TP") (pinfunction "TP_TP") (pintype "input"))
      (node (ref "U4") (pin "2") (pinfunction "CELL_2") (pintype "power_in"))
      (node (ref "U4") (pin "3") (pinfunction "VDD_3") (pintype "power_in"))
    )
    (net (code "53") (name "VBUS") (class "Default")
      (node (ref "C1_BAT") (pin "1") (pinfunction "1_1") (pintype "passive"))
      (node (ref "C4_USB") (pin "1") (pinfunction "1_1") (pintype "passive"))
      (node (ref "C5_USB") (pin "1") (pinfunction "1_1") (pintype "passive"))
      (node (ref "CHG_LED") (pin "A") (pinfunction "A_A") (pintype "passive"))
      (node (ref "D1") (pin "5") (pinfunction "VBUS_5") (pintype "bidirectional"))
      (node (ref "D2") (pin "2") (pinfunction "ANODE_2") (pintype "bidirectional"))
      (node (ref "MCP73831") (pin "4") (pinfunction "VIN_4") (pintype "power_in"))
      (node (ref "PFMF.050.1") (pin "2") (pinfunction "2_2") (pintype "passive"))
      (node (ref "Q1") (pin "1") (pinfunction "G_1") (pintype "bidirectional"))
      (node (ref "R1_PWRUSB") (pin "2") (pinfunction "2_2") (pintype "passive"))
      (node (ref "TPVBUS") (pin "TP") (pinfunction "TP_TP") (pintype "input"))
    )
    (net (code "54") (name "VRTC") (class "Default")
      (node (ref "C11") (pin "1") (pinfunction "1_1") (pintype "passive"))
      (node (ref "C8") (pin "1") (pinfunction "1_1") (pintype "passive"))
      (node (ref "R_CAPACITOR") (pin "2") (pinfunction "2_2") (pintype "passive"))
      (node (ref "U3") (pin "14") (pinfunction "VBAT_14") (pintype "power_in"))
    )
    (net (code "55") (name "VUSB") (class "Default")
      (node (ref "J2") (pin "A4") (pinfunction "A4_A4") (pintype "bidirectional"))
      (node (ref "J2") (pin "A9") (pinfunction "A9_A9") (pintype "bidirectional"))
      (node (ref "J2") (pin "B4") (pinfunction "B4_B4") (pintype "bidirectional"))
      (node (ref "J2") (pin "B9") (pinfunction "B9_B9") (pintype "bidirectional"))
      (node (ref "PFMF.050.1") (pin "1") (pinfunction "1_1") (pintype "passive"))
    )
    (net (code "56") (name "unconnected-(IC1-NC-Pad4)") (class "Default")
      (node (ref "IC1") (pin "4") (pinfunction "NC_4") (pintype "no_connect"))
    )
    (net (code "57") (name "unconnected-(IC4-NC-Pad4)") (class "Default")
      (node (ref "IC4") (pin "4") (pinfunction "NC_4") (pintype "no_connect"))
    )
    (net (code "58") (name "unconnected-(J1-Pad1)") (class "Default")
      (node (ref "J1") (pin "1") (pinfunction "1_1") (pintype "bidirectional"))
    )
    (net (code "59") (name "unconnected-(J1-Pad6)") (class "Default")
      (node (ref "J1") (pin "6") (pinfunction "6_6") (pintype "bidirectional"))
    )
    (net (code "60") (name "unconnected-(J1-Pad7)") (class "Default")
      (node (ref "J1") (pin "7") (pinfunction "7_7") (pintype "bidirectional"))
    )
    (net (code "61") (name "unconnected-(J2-PadA8)") (class "Default")
      (node (ref "J2") (pin "A8") (pinfunction "A8_A8") (pintype "bidirectional"))
    )
    (net (code "62") (name "unconnected-(J2-PadB8)") (class "Default")
      (node (ref "J2") (pin "B8") (pinfunction "B8_B8") (pintype "bidirectional"))
    )
    (net (code "63") (name "unconnected-(J4-DAT1-PadP8)") (class "Default")
      (node (ref "J4") (pin "P8") (pinfunction "DAT1_P8") (pintype "bidirectional"))
    )
    (net (code "64") (name "unconnected-(J4-DAT2-PadP1)") (class "Default")
      (node (ref "J4") (pin "P1") (pinfunction "DAT2_P1") (pintype "bidirectional"))
    )
    (net (code "65") (name "unconnected-(J4-DETECTION_1-PadS1)") (class "Default")
      (node (ref "J4") (pin "S1") (pinfunction "DETECTION_1_S1") (pintype "bidirectional"))
    )
    (net (code "66") (name "unconnected-(J4-DETECTION_2-PadS2)") (class "Default")
      (node (ref "J4") (pin "S2") (pinfunction "DETECTION_2_S2") (pintype "bidirectional"))
    )
    (net (code "67") (name "unconnected-(U2-NC-Pad22)") (class "Default")
      (node (ref "U2") (pin "22") (pinfunction "NC_22") (pintype "no_connect"))
    )
    (net (code "68") (name "unconnected-(U4-~{ALERT}-Pad5)") (class "Default")
      (node (ref "U4") (pin "5") (pinfunction "~{ALERT}_5") (pintype "output"))
    )
  )
)
